# Macro_Watch.net
KiCad netlist of a schematic drawn in EAGLE
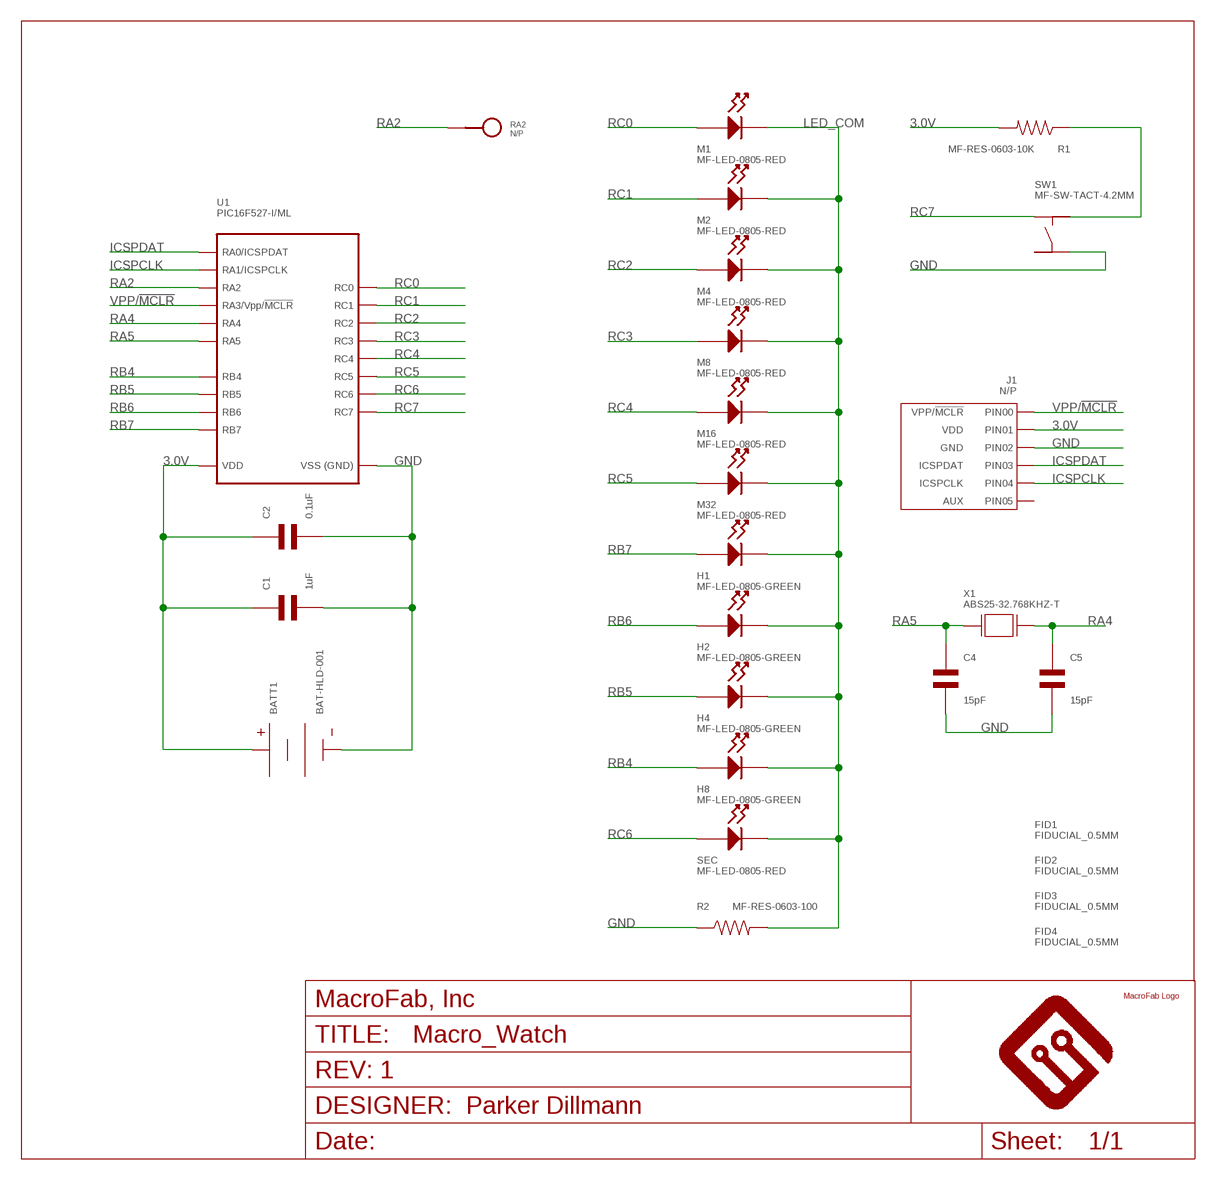
[diagram p0: schematic, sheet 1]

(export (version "E")
  (design (tool "Eeschema 10.0.6"))
  (components
    (comp (ref "BATT1")
      (value "BAT-HLD-001")
      (footprint "eagle-import:BAT-HLD-001")
      (libsource (lib "eagle-import") (part "BATTERY_BAT-HLD-001"))
    )
    (comp (ref "C1")
      (value "1uF")
      (footprint "eagle-import:C0603")
      (libsource (lib "eagle-import") (part "CAPACITOR_NP_0603"))
    )
    (comp (ref "C2")
      (value "0.1uF")
      (footprint "eagle-import:C0603")
      (libsource (lib "eagle-import") (part "CAPACITOR_NP_0603"))
    )
    (comp (ref "C4")
      (value "15pF")
      (footprint "eagle-import:C0603")
      (libsource (lib "eagle-import") (part "CAPACITOR_NP_0603"))
    )
    (comp (ref "C5")
      (value "15pF")
      (footprint "eagle-import:C0603")
      (libsource (lib "eagle-import") (part "CAPACITOR_NP_0603"))
    )
    (comp (ref "FID1")
      (value "FIDUCIAL_0.5MM")
      (footprint "eagle-import:FIDUCIAL_0.5MM")
      (libsource (lib "eagle-import") (part "FIDUCIAL_0.5MM"))
    )
    (comp (ref "FID2")
      (value "FIDUCIAL_0.5MM")
      (footprint "eagle-import:FIDUCIAL_0.5MM")
      (libsource (lib "eagle-import") (part "FIDUCIAL_0.5MM"))
    )
    (comp (ref "FID3")
      (value "FIDUCIAL_0.5MM")
      (footprint "eagle-import:FIDUCIAL_0.5MM")
      (libsource (lib "eagle-import") (part "FIDUCIAL_0.5MM"))
    )
    (comp (ref "FID4")
      (value "FIDUCIAL_0.5MM")
      (footprint "eagle-import:FIDUCIAL_0.5MM")
      (libsource (lib "eagle-import") (part "FIDUCIAL_0.5MM"))
    )
    (comp (ref "FRAME1")
      (value "MF_FRAMEDEFAULT")
      (footprint "eagle-import:MF_FRAME_DEFAULT")
      (fields (field (name "DNAME") "Parker Dillmann") (field (name "REVNUM") "REV: 1"))
      (libsource (lib "eagle-import") (part "MF_FRAMEDEFAULT"))
    )
    (comp (ref "H1")
      (value "MF-LED-0805-GREEN")
      (footprint "eagle-import:LED0805")
      (libsource (lib "eagle-import") (part "LED_SINGLE_0805"))
    )
    (comp (ref "H2")
      (value "MF-LED-0805-GREEN")
      (footprint "eagle-import:LED0805")
      (libsource (lib "eagle-import") (part "LED_SINGLE_0805"))
    )
    (comp (ref "H4")
      (value "MF-LED-0805-GREEN")
      (footprint "eagle-import:LED0805")
      (libsource (lib "eagle-import") (part "LED_SINGLE_0805"))
    )
    (comp (ref "H8")
      (value "MF-LED-0805-GREEN")
      (footprint "eagle-import:LED0805")
      (libsource (lib "eagle-import") (part "LED_SINGLE_0805"))
    )
    (comp (ref "J1")
      (value "N/P")
      (footprint "eagle-import:PTH_2.54MM_01X06")
      (fields
        (field (name "LABEL00") "VPP/!MCLR")
        (field (name "LABEL01") "VDD")
        (field (name "LABEL02") "GND")
        (field (name "LABEL03") "ICSPDAT")
        (field (name "LABEL04") "ICSPCLK")
        (field (name "LABEL05") "AUX")
      )
      (libsource (lib "eagle-import") (part "HEADER_01X06_PTH_2.54MM"))
    )
    (comp (ref "M1")
      (value "MF-LED-0805-RED")
      (footprint "eagle-import:LED0805")
      (libsource (lib "eagle-import") (part "LED_SINGLE_0805"))
    )
    (comp (ref "M2")
      (value "MF-LED-0805-RED")
      (footprint "eagle-import:LED0805")
      (libsource (lib "eagle-import") (part "LED_SINGLE_0805"))
    )
    (comp (ref "M4")
      (value "MF-LED-0805-RED")
      (footprint "eagle-import:LED0805")
      (libsource (lib "eagle-import") (part "LED_SINGLE_0805"))
    )
    (comp (ref "M8")
      (value "MF-LED-0805-RED")
      (footprint "eagle-import:LED0805")
      (libsource (lib "eagle-import") (part "LED_SINGLE_0805"))
    )
    (comp (ref "M16")
      (value "MF-LED-0805-RED")
      (footprint "eagle-import:LED0805")
      (libsource (lib "eagle-import") (part "LED_SINGLE_0805"))
    )
    (comp (ref "M32")
      (value "MF-LED-0805-RED")
      (footprint "eagle-import:LED0805")
      (libsource (lib "eagle-import") (part "LED_SINGLE_0805"))
    )
    (comp (ref "R1")
      (value "MF-RES-0603-10K")
      (footprint "eagle-import:R0603")
      (libsource (lib "eagle-import") (part "RESISTOR_0603"))
    )
    (comp (ref "R2")
      (value "MF-RES-0603-100")
      (footprint "eagle-import:R0603")
      (libsource (lib "eagle-import") (part "RESISTOR_0603"))
    )
    (comp (ref "RA2")
      (value "N/P")
      (footprint "eagle-import:ROUND_TP")
      (libsource (lib "eagle-import") (part "TEST_POINT_SINGLE_ROUND_1MM"))
    )
    (comp (ref "SEC")
      (value "MF-LED-0805-RED")
      (footprint "eagle-import:LED0805")
      (libsource (lib "eagle-import") (part "LED_SINGLE_0805"))
    )
    (comp (ref "SW1")
      (value "MF-SW-TACT-4.2MM")
      (footprint "eagle-import:TACT4.2MM")
      (libsource (lib "eagle-import") (part "TACT_4.2MM"))
    )
    (comp (ref "U$1")
      (value "MF_LOGOLOGO_SMALL")
      (footprint "eagle-import:MF_LOGO_SMALL")
      (libsource (lib "eagle-import") (part "MF_LOGOLOGO_SMALL"))
    )
    (comp (ref "U1")
      (value "PIC16F527-I/ML")
      (footprint "eagle-import:QFN20")
      (libsource (lib "eagle-import") (part "PIC16F527-I/ML"))
    )
    (comp (ref "X1")
      (value "ABS25-32.768KHZ-T")
      (footprint "eagle-import:ABS25_SERIES")
      (libsource (lib "eagle-import") (part "ABS25"))
    )
  )
  (nets
    (net (code "1") (name "/3.0V") (class "Default")
      (node (ref "BATT1") (pin "POS_0") (pinfunction "POS_POS_0") (pintype "bidirectional"))
      (node (ref "BATT1") (pin "POS_1") (pinfunction "POS_POS_1") (pintype "bidirectional"))
      (node (ref "C1") (pin "P$1") (pinfunction "P$1_P$1") (pintype "passive"))
      (node (ref "C2") (pin "P$1") (pinfunction "P$1_P$1") (pintype "passive"))
      (node (ref "J1") (pin "P$2") (pinfunction "PIN1_P$2") (pintype "bidirectional"))
      (node (ref "R1") (pin "P$2") (pinfunction "P$2_P$2") (pintype "passive"))
      (node (ref "U1") (pin "P$18") (pinfunction "VDD_P$18") (pintype "power_in"))
    )
    (net (code "2") (name "/GND") (class "Default")
      (node (ref "BATT1") (pin "NEG_0") (pinfunction "NEG_NEG_0") (pintype "bidirectional"))
      (node (ref "C1") (pin "P$2") (pinfunction "P$2_P$2") (pintype "passive"))
      (node (ref "C2") (pin "P$2") (pinfunction "P$2_P$2") (pintype "passive"))
      (node (ref "C4") (pin "P$2") (pinfunction "P$2_P$2") (pintype "passive"))
      (node (ref "C5") (pin "P$2") (pinfunction "P$2_P$2") (pintype "passive"))
      (node (ref "J1") (pin "P$3") (pinfunction "PIN2_P$3") (pintype "bidirectional"))
      (node (ref "R2") (pin "P$1") (pinfunction "P$1_P$1") (pintype "passive"))
      (node (ref "SW1") (pin "P$4") (pinfunction "P$4_P$4") (pintype "bidirectional"))
      (node (ref "U1") (pin "P$17") (pinfunction "GND_P$17") (pintype "power_in"))
    )
    (net (code "3") (name "/ICSPCLK") (class "Default")
      (node (ref "J1") (pin "P$5") (pinfunction "PIN4_P$5") (pintype "bidirectional"))
      (node (ref "U1") (pin "P$15") (pinfunction "RA1/ICSPCLK_P$15") (pintype "bidirectional"))
    )
    (net (code "4") (name "/ICSPDAT") (class "Default")
      (node (ref "J1") (pin "P$4") (pinfunction "PIN3_P$4") (pintype "bidirectional"))
      (node (ref "U1") (pin "P$16") (pinfunction "RA0/ICSPDAT_P$16") (pintype "bidirectional"))
    )
    (net (code "5") (name "/LED_COM") (class "Default")
      (node (ref "H1") (pin "CATHODE") (pinfunction "CATHODE_CATHODE") (pintype "power_in"))
      (node (ref "H2") (pin "CATHODE") (pinfunction "CATHODE_CATHODE") (pintype "power_in"))
      (node (ref "H4") (pin "CATHODE") (pinfunction "CATHODE_CATHODE") (pintype "power_in"))
      (node (ref "H8") (pin "CATHODE") (pinfunction "CATHODE_CATHODE") (pintype "power_in"))
      (node (ref "M1") (pin "CATHODE") (pinfunction "CATHODE_CATHODE") (pintype "power_in"))
      (node (ref "M16") (pin "CATHODE") (pinfunction "CATHODE_CATHODE") (pintype "power_in"))
      (node (ref "M2") (pin "CATHODE") (pinfunction "CATHODE_CATHODE") (pintype "power_in"))
      (node (ref "M32") (pin "CATHODE") (pinfunction "CATHODE_CATHODE") (pintype "power_in"))
      (node (ref "M4") (pin "CATHODE") (pinfunction "CATHODE_CATHODE") (pintype "power_in"))
      (node (ref "M8") (pin "CATHODE") (pinfunction "CATHODE_CATHODE") (pintype "power_in"))
      (node (ref "R2") (pin "P$2") (pinfunction "P$2_P$2") (pintype "passive"))
      (node (ref "SEC") (pin "CATHODE") (pinfunction "CATHODE_CATHODE") (pintype "power_in"))
    )
    (net (code "6") (name "/RA2") (class "Default")
      (node (ref "RA2") (pin "P$1") (pinfunction "P$1_P$1") (pintype "bidirectional"))
      (node (ref "U1") (pin "P$14") (pinfunction "RA2_P$14") (pintype "bidirectional"))
    )
    (net (code "7") (name "/RA4") (class "Default")
      (node (ref "C5") (pin "P$1") (pinfunction "P$1_P$1") (pintype "passive"))
      (node (ref "U1") (pin "P$20") (pinfunction "RA4_P$20") (pintype "bidirectional"))
      (node (ref "X1") (pin "4") (pinfunction "X1_4") (pintype "bidirectional"))
    )
    (net (code "8") (name "/RA5") (class "Default")
      (node (ref "C4") (pin "P$1") (pinfunction "P$1_P$1") (pintype "passive"))
      (node (ref "U1") (pin "P$19") (pinfunction "RA5_P$19") (pintype "bidirectional"))
      (node (ref "X1") (pin "1") (pinfunction "X0_1") (pintype "bidirectional"))
    )
    (net (code "9") (name "/RB4") (class "Default")
      (node (ref "H8") (pin "ANODE") (pinfunction "ANODE_ANODE") (pintype "power_in"))
      (node (ref "U1") (pin "P$10") (pinfunction "RB4_P$10") (pintype "bidirectional"))
    )
    (net (code "10") (name "/RB5") (class "Default")
      (node (ref "H4") (pin "ANODE") (pinfunction "ANODE_ANODE") (pintype "power_in"))
      (node (ref "U1") (pin "P$9") (pinfunction "RB5_P$9") (pintype "bidirectional"))
    )
    (net (code "11") (name "/RB6") (class "Default")
      (node (ref "H2") (pin "ANODE") (pinfunction "ANODE_ANODE") (pintype "power_in"))
      (node (ref "U1") (pin "P$8") (pinfunction "RB6_P$8") (pintype "bidirectional"))
    )
    (net (code "12") (name "/RB7") (class "Default")
      (node (ref "H1") (pin "ANODE") (pinfunction "ANODE_ANODE") (pintype "power_in"))
      (node (ref "U1") (pin "P$7") (pinfunction "RB7_P$7") (pintype "bidirectional"))
    )
    (net (code "13") (name "/RC0") (class "Default")
      (node (ref "M1") (pin "ANODE") (pinfunction "ANODE_ANODE") (pintype "power_in"))
      (node (ref "U1") (pin "P$13") (pinfunction "RC0_P$13") (pintype "bidirectional"))
    )
    (net (code "14") (name "/RC1") (class "Default")
      (node (ref "M2") (pin "ANODE") (pinfunction "ANODE_ANODE") (pintype "power_in"))
      (node (ref "U1") (pin "P$12") (pinfunction "RC1_P$12") (pintype "bidirectional"))
    )
    (net (code "15") (name "/RC2") (class "Default")
      (node (ref "M4") (pin "ANODE") (pinfunction "ANODE_ANODE") (pintype "power_in"))
      (node (ref "U1") (pin "P$11") (pinfunction "RC2_P$11") (pintype "bidirectional"))
    )
    (net (code "16") (name "/RC3") (class "Default")
      (node (ref "M8") (pin "ANODE") (pinfunction "ANODE_ANODE") (pintype "power_in"))
      (node (ref "U1") (pin "P$4") (pinfunction "RC3_P$4") (pintype "bidirectional"))
    )
    (net (code "17") (name "/RC4") (class "Default")
      (node (ref "M16") (pin "ANODE") (pinfunction "ANODE_ANODE") (pintype "power_in"))
      (node (ref "U1") (pin "P$3") (pinfunction "RC4_P$3") (pintype "bidirectional"))
    )
    (net (code "18") (name "/RC5") (class "Default")
      (node (ref "M32") (pin "ANODE") (pinfunction "ANODE_ANODE") (pintype "power_in"))
      (node (ref "U1") (pin "P$2") (pinfunction "RC5_P$2") (pintype "bidirectional"))
    )
    (net (code "19") (name "/RC6") (class "Default")
      (node (ref "SEC") (pin "ANODE") (pinfunction "ANODE_ANODE") (pintype "power_in"))
      (node (ref "U1") (pin "P$5") (pinfunction "RC6_P$5") (pintype "bidirectional"))
    )
    (net (code "20") (name "/RC7") (class "Default")
      (node (ref "SW1") (pin "P$1") (pinfunction "P$1_P$1") (pintype "bidirectional"))
      (node (ref "U1") (pin "P$6") (pinfunction "RC7_P$6") (pintype "bidirectional"))
    )
    (net (code "21") (name "/VPP{slash}~{MCLR}") (class "Default")
      (node (ref "J1") (pin "P$1") (pinfunction "PIN0_P$1") (pintype "bidirectional"))
      (node (ref "U1") (pin "P$1") (pinfunction "RA3/VPP/~{MCLR}_P$1") (pintype "bidirectional"))
    )
    (net (code "22") (name "Net-(R1-PadP$1)") (class "Default")
      (node (ref "R1") (pin "P$1") (pinfunction "P$1_P$1") (pintype "passive"))
      (node (ref "SW1") (pin "P$2") (pinfunction "P$2_P$2") (pintype "bidirectional"))
    )
    (net (code "23") (name "unconnected-(J1-PIN5-PadP$6)") (class "Default")
      (node (ref "J1") (pin "P$6") (pinfunction "PIN5_P$6") (pintype "bidirectional"))
    )
    (net (code "24") (name "unconnected-(SW1-PadP$3)") (class "Default")
      (node (ref "SW1") (pin "P$3") (pinfunction "P$3_P$3") (pintype "bidirectional"))
    )
  )
)
